# schematic.net
KiCad netlist of a schematic drawn in EAGLE
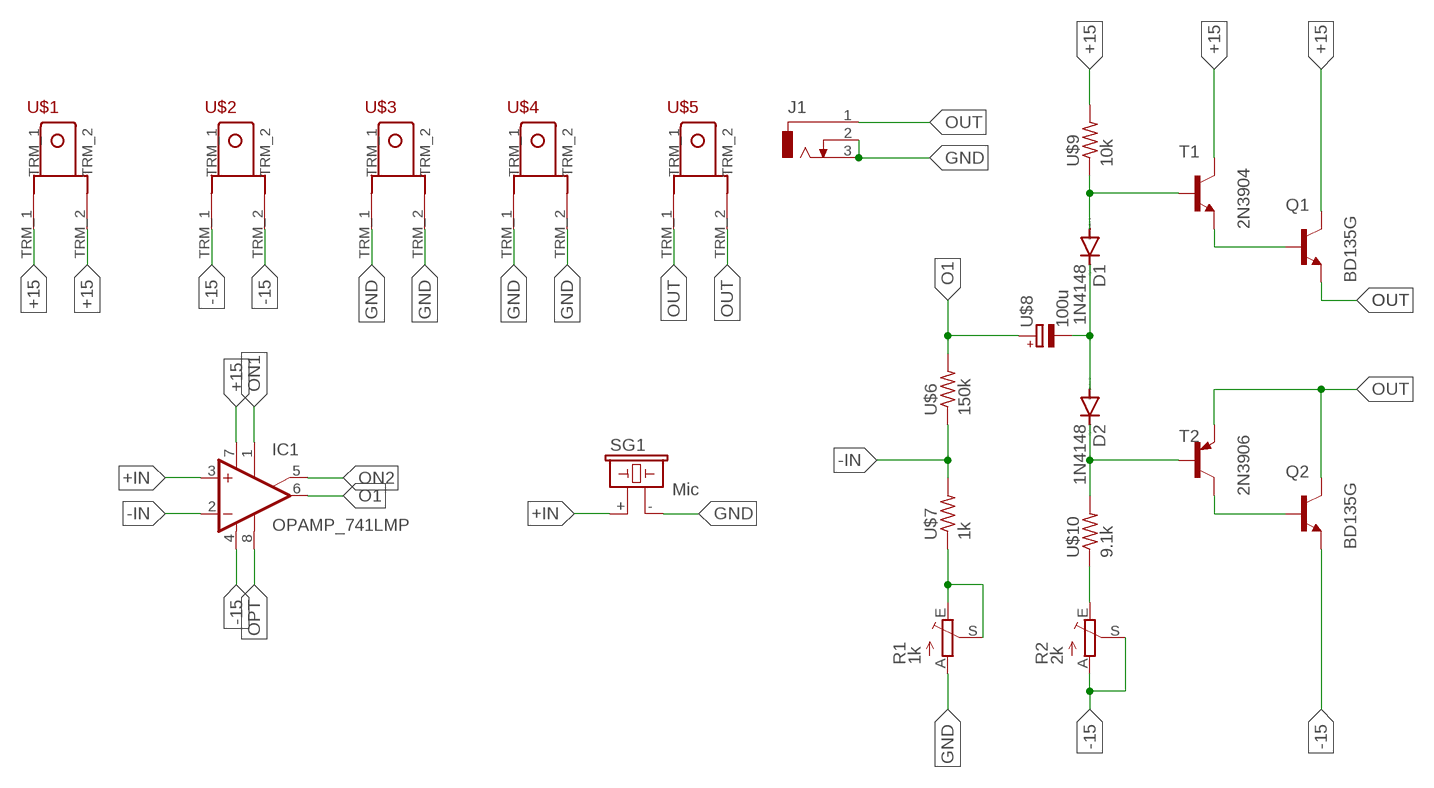
[diagram p0: schematic, sheet 1]

(export (version "E")
  (design (tool "Eeschema 10.0.6"))
  (components
    (comp (ref "D1")
      (value "1N4148")
      (footprint "eagle-import:DO35-10")
      (libsource (lib "eagle-import") (part "1N4148DO35-10"))
    )
    (comp (ref "D2")
      (value "1N4148")
      (footprint "eagle-import:DO35-10")
      (libsource (lib "eagle-import") (part "1N4148DO35-10"))
    )
    (comp (ref "IC1")
      (value "OPAMP_741LMP")
      (footprint "eagle-import:DIL08")
      (libsource (lib "eagle-import") (part "OPAMP_741PLM"))
    )
    (comp (ref "J1")
      (value "CON_JACK")
      (footprint "eagle-import:DCJ0303")
      (libsource (lib "eagle-import") (part "CON_JACK"))
    )
    (comp (ref "Q1")
      (value "BD135G")
      (footprint "eagle-import:TO229P780X300X2000-3")
      (fields (field (name "MF") "ON Semiconductor"))
      (libsource (lib "eagle-import") (part "BD135G"))
    )
    (comp (ref "Q2")
      (value "BD135G")
      (footprint "eagle-import:TO229P780X300X2000-3")
      (fields (field (name "MF") "ON Semiconductor"))
      (libsource (lib "eagle-import") (part "BD135G"))
    )
    (comp (ref "R1")
      (value "1k")
      (footprint "eagle-import:CA6V")
      (libsource (lib "eagle-import") (part "TRIM_EU-CA6V"))
    )
    (comp (ref "R2")
      (value "2k")
      (footprint "eagle-import:CA6V")
      (libsource (lib "eagle-import") (part "TRIM_EU-CA6V"))
    )
    (comp (ref "SG1")
      (value "Mic")
      (footprint "eagle-import:F_CM12P")
      (libsource (lib "eagle-import") (part "BUZZER"))
    )
    (comp (ref "T1")
      (value "2N3904")
      (footprint "eagle-import:TO92-EBC")
      (libsource (lib "eagle-import") (part "-NPN-TO92-EBC2N3904"))
    )
    (comp (ref "T2")
      (value "2N3906")
      (footprint "eagle-import:TO92-EBC")
      (libsource (lib "eagle-import") (part "-PNP-TO92-EBC2N3906"))
    )
    (comp (ref "U$1")
      (value "TERMINAL_EDITED")
      (footprint "eagle-import:TERMINAL_EDITED")
      (libsource (lib "eagle-import") (part "TERMINAL_EDITED"))
    )
    (comp (ref "U$2")
      (value "TERMINAL_EDITED")
      (footprint "eagle-import:TERMINAL_EDITED")
      (libsource (lib "eagle-import") (part "TERMINAL_EDITED"))
    )
    (comp (ref "U$3")
      (value "TERMINAL_EDITED")
      (footprint "eagle-import:TERMINAL_EDITED")
      (libsource (lib "eagle-import") (part "TERMINAL_EDITED"))
    )
    (comp (ref "U$4")
      (value "TERMINAL_EDITED")
      (footprint "eagle-import:TERMINAL_EDITED")
      (libsource (lib "eagle-import") (part "TERMINAL_EDITED"))
    )
    (comp (ref "U$5")
      (value "TERMINAL_EDITED")
      (footprint "eagle-import:TERMINAL_EDITED")
      (libsource (lib "eagle-import") (part "TERMINAL_EDITED"))
    )
    (comp (ref "U$6")
      (value "150k")
      (footprint "eagle-import:0204_7")
      (libsource (lib "eagle-import") (part "RES-7"))
    )
    (comp (ref "U$7")
      (value "1k")
      (footprint "eagle-import:0204_7")
      (libsource (lib "eagle-import") (part "RES-7"))
    )
    (comp (ref "U$8")
      (value "100u")
      (footprint "eagle-import:E3,5-8")
      (libsource (lib "eagle-import") (part "CAP_POL"))
    )
    (comp (ref "U$9")
      (value "10k")
      (footprint "eagle-import:0204_7")
      (libsource (lib "eagle-import") (part "RES-7"))
    )
    (comp (ref "U$10")
      (value "9.1k")
      (footprint "eagle-import:0204_7")
      (libsource (lib "eagle-import") (part "RES-7"))
    )
  )
  (nets
    (net (code "1") (name "+15") (class "Default")
      (node (ref "IC1") (pin "7") (pinfunction "V+_7") (pintype "power_in"))
      (node (ref "Q1") (pin "2") (pinfunction "C_2") (pintype "passive"))
      (node (ref "T1") (pin "C") (pinfunction "C_C") (pintype "passive"))
      (node (ref "U$1") (pin "TRM_1") (pinfunction "TRM_1_TRM_1") (pintype "bidirectional"))
      (node (ref "U$1") (pin "TRM_2") (pinfunction "TRM_2_TRM_2") (pintype "bidirectional"))
      (node (ref "U$9") (pin "2") (pinfunction "2_2") (pintype "passive"))
    )
    (net (code "2") (name "+IN") (class "Default")
      (node (ref "IC1") (pin "3") (pinfunction "+IN_3") (pintype "input"))
      (node (ref "SG1") (pin "+") (pinfunction "1_+") (pintype "passive"))
    )
    (net (code "3") (name "-15") (class "Default")
      (node (ref "IC1") (pin "4") (pinfunction "V-_4") (pintype "power_in"))
      (node (ref "Q2") (pin "1") (pinfunction "E_1") (pintype "passive"))
      (node (ref "R2") (pin "A") (pinfunction "A_A") (pintype "passive"))
      (node (ref "R2") (pin "S") (pinfunction "S_S") (pintype "passive"))
      (node (ref "U$2") (pin "TRM_1") (pinfunction "TRM_1_TRM_1") (pintype "bidirectional"))
      (node (ref "U$2") (pin "TRM_2") (pinfunction "TRM_2_TRM_2") (pintype "bidirectional"))
    )
    (net (code "4") (name "-IN") (class "Default")
      (node (ref "IC1") (pin "2") (pinfunction "-IN_2") (pintype "input"))
      (node (ref "U$6") (pin "1") (pinfunction "1_1") (pintype "passive"))
      (node (ref "U$7") (pin "2") (pinfunction "2_2") (pintype "passive"))
    )
    (net (code "5") (name "GND") (class "Default")
      (node (ref "J1") (pin "2") (pinfunction "2_2") (pintype "passive"))
      (node (ref "J1") (pin "3") (pinfunction "3_3") (pintype "passive"))
      (node (ref "R1") (pin "A") (pinfunction "A_A") (pintype "passive"))
      (node (ref "SG1") (pin "-") (pinfunction "2_-") (pintype "passive"))
      (node (ref "U$3") (pin "TRM_1") (pinfunction "TRM_1_TRM_1") (pintype "bidirectional"))
      (node (ref "U$3") (pin "TRM_2") (pinfunction "TRM_2_TRM_2") (pintype "bidirectional"))
      (node (ref "U$4") (pin "TRM_1") (pinfunction "TRM_1_TRM_1") (pintype "bidirectional"))
      (node (ref "U$4") (pin "TRM_2") (pinfunction "TRM_2_TRM_2") (pintype "bidirectional"))
    )
    (net (code "6") (name "Net-(D1-PadA)") (class "Default")
      (node (ref "D1") (pin "A") (pinfunction "A_A") (pintype "passive"))
      (node (ref "T1") (pin "B") (pinfunction "B_B") (pintype "passive"))
      (node (ref "U$9") (pin "1") (pinfunction "1_1") (pintype "passive"))
    )
    (net (code "7") (name "Net-(D1-PadC)") (class "Default")
      (node (ref "D1") (pin "C") (pinfunction "C_C") (pintype "passive"))
      (node (ref "D2") (pin "A") (pinfunction "A_A") (pintype "passive"))
      (node (ref "U$8") (pin "-") (pinfunction "-_-") (pintype "passive"))
    )
    (net (code "8") (name "Net-(D2-PadC)") (class "Default")
      (node (ref "D2") (pin "C") (pinfunction "C_C") (pintype "passive"))
      (node (ref "T2") (pin "B") (pinfunction "B_B") (pintype "passive"))
      (node (ref "U$10") (pin "2") (pinfunction "2_2") (pintype "passive"))
    )
    (net (code "9") (name "Net-(Q1-B)") (class "Default")
      (node (ref "Q1") (pin "3") (pinfunction "B_3") (pintype "passive"))
      (node (ref "T1") (pin "E") (pinfunction "E_E") (pintype "passive"))
    )
    (net (code "10") (name "Net-(Q2-B)") (class "Default")
      (node (ref "Q2") (pin "3") (pinfunction "B_3") (pintype "passive"))
      (node (ref "T2") (pin "C") (pinfunction "C_C") (pintype "passive"))
    )
    (net (code "11") (name "Net-(R1-PadE)") (class "Default")
      (node (ref "R1") (pin "E") (pinfunction "E_E") (pintype "passive"))
      (node (ref "R1") (pin "S") (pinfunction "S_S") (pintype "passive"))
      (node (ref "U$7") (pin "1") (pinfunction "1_1") (pintype "passive"))
    )
    (net (code "12") (name "Net-(R2-PadE)") (class "Default")
      (node (ref "R2") (pin "E") (pinfunction "E_E") (pintype "passive"))
      (node (ref "U$10") (pin "1") (pinfunction "1_1") (pintype "passive"))
    )
    (net (code "13") (name "O1") (class "Default")
      (node (ref "IC1") (pin "6") (pinfunction "OUT_6") (pintype "output"))
      (node (ref "U$6") (pin "2") (pinfunction "2_2") (pintype "passive"))
      (node (ref "U$8") (pin "+") (pinfunction "+_+") (pintype "passive"))
    )
    (net (code "14") (name "ON1") (class "Default")
      (node (ref "IC1") (pin "1") (pinfunction "ON1_1") (pintype "passive"))
    )
    (net (code "15") (name "ON2") (class "Default")
      (node (ref "IC1") (pin "5") (pinfunction "ON2_5") (pintype "passive"))
    )
    (net (code "16") (name "OPT") (class "Default")
      (node (ref "IC1") (pin "8") (pinfunction "OPT_8") (pintype "passive"))
    )
    (net (code "17") (name "OUT") (class "Default")
      (node (ref "J1") (pin "1") (pinfunction "1_1") (pintype "passive"))
      (node (ref "Q1") (pin "1") (pinfunction "E_1") (pintype "passive"))
      (node (ref "Q2") (pin "2") (pinfunction "C_2") (pintype "passive"))
      (node (ref "T2") (pin "E") (pinfunction "E_E") (pintype "passive"))
      (node (ref "U$5") (pin "TRM_1") (pinfunction "TRM_1_TRM_1") (pintype "bidirectional"))
      (node (ref "U$5") (pin "TRM_2") (pinfunction "TRM_2_TRM_2") (pintype "bidirectional"))
    )
  )
)
